# DigiCar.net
KiCad netlist of a schematic drawn in EAGLE
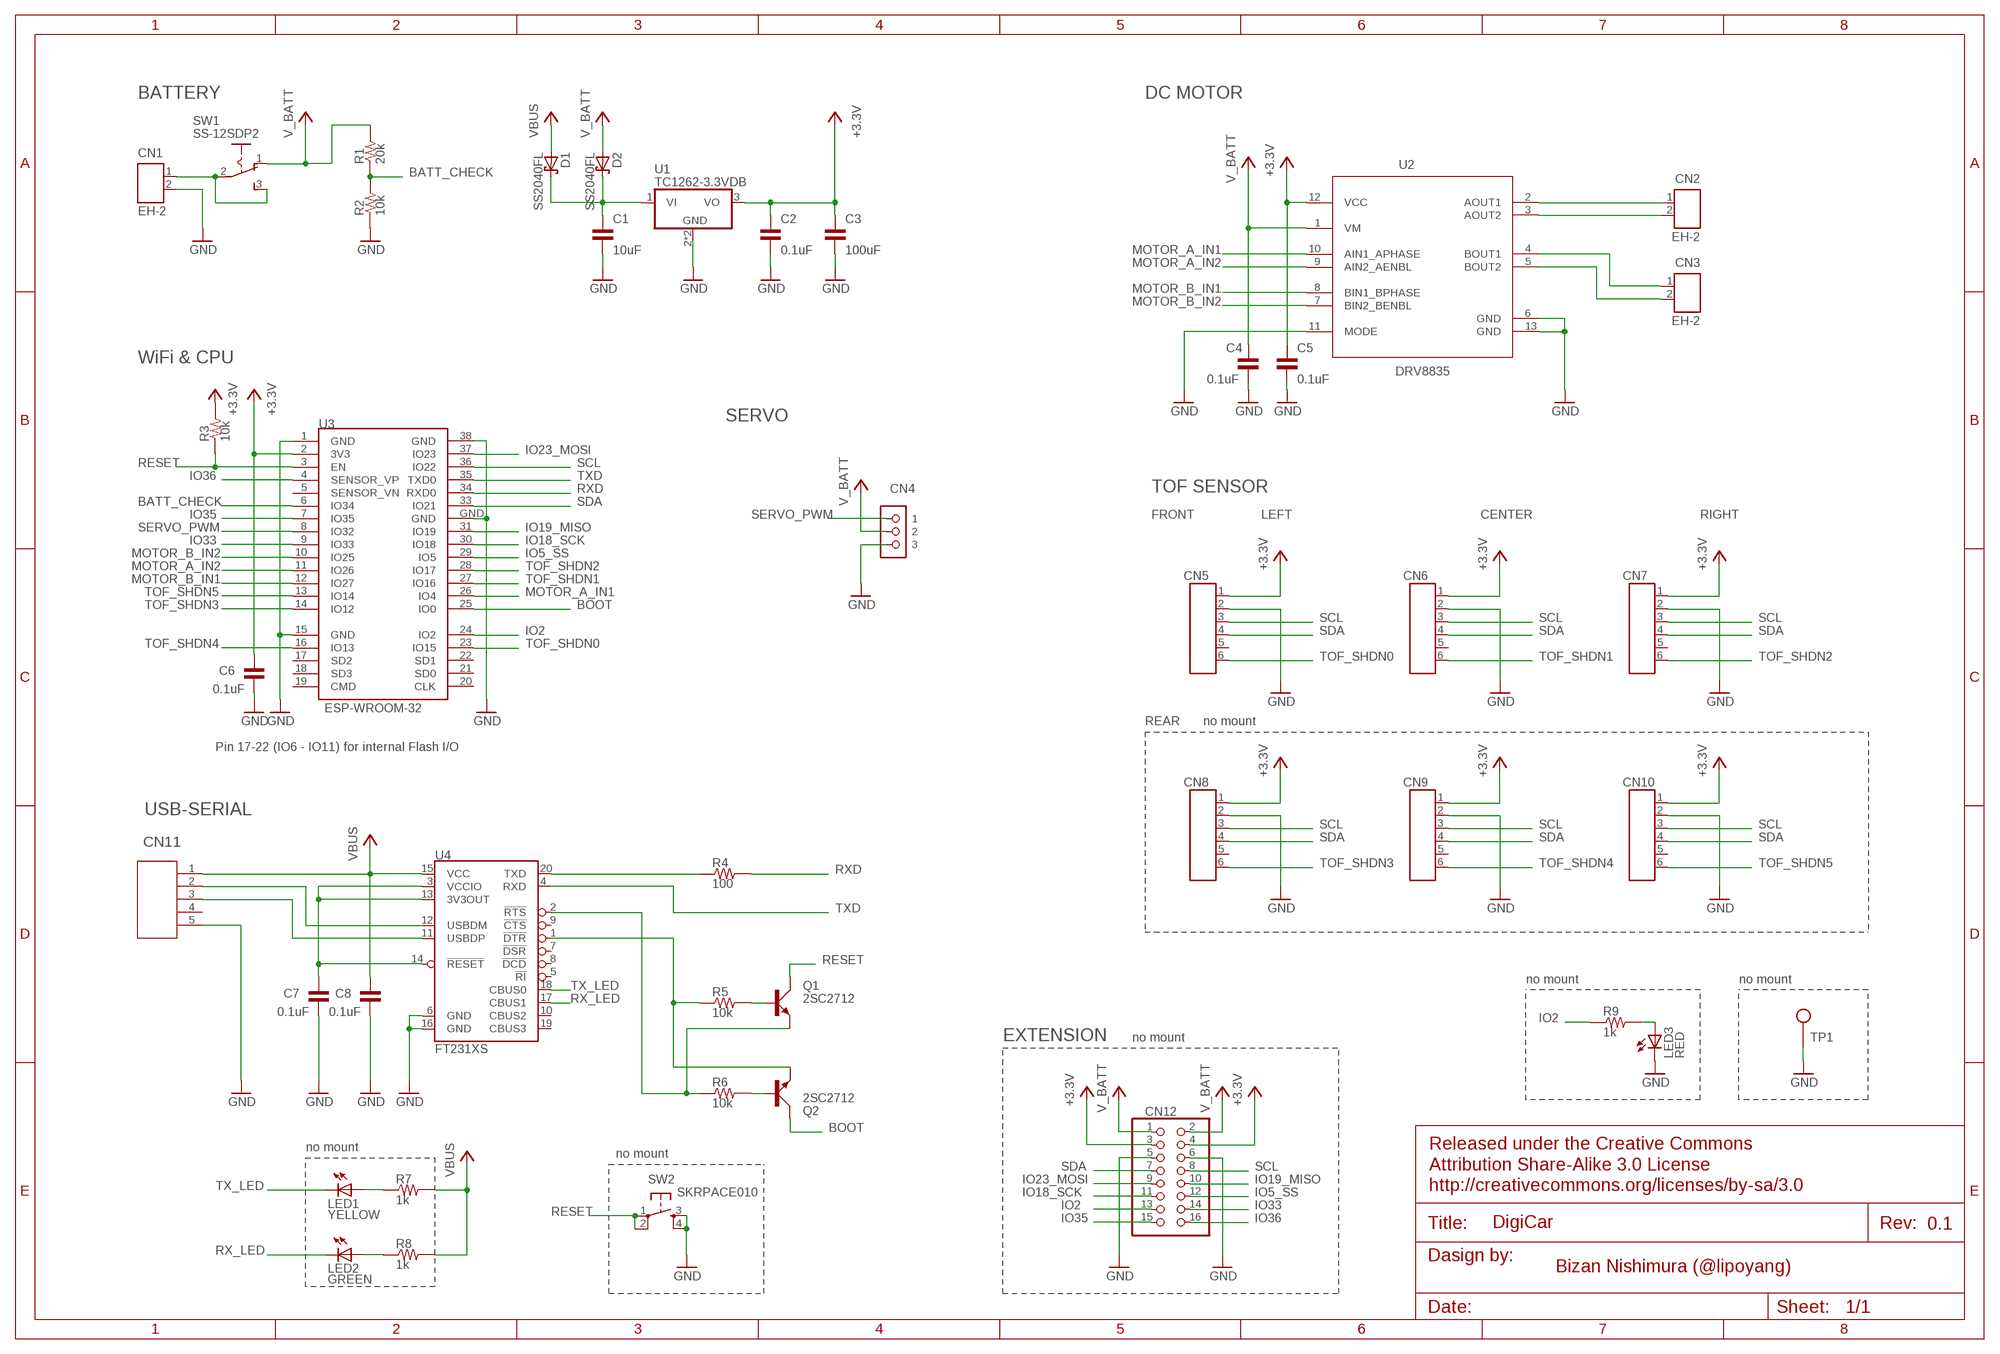
[diagram p0: schematic, sheet 1]

(export (version "E")
  (design (tool "Eeschema 10.0.6"))
  (components
    (comp (ref "C1")
      (value "10uF")
      (footprint "eagle-import:CP3216")
      (libsource (lib "eagle-import") (part "C-CP-3216"))
    )
    (comp (ref "C2")
      (value "0.1uF")
      (footprint "eagle-import:CP1608")
      (libsource (lib "eagle-import") (part "C-CP-1608"))
    )
    (comp (ref "C3")
      (value "100uF")
      (footprint "eagle-import:CP3216")
      (libsource (lib "eagle-import") (part "C-CP-3216"))
    )
    (comp (ref "C4")
      (value "0.1uF")
      (footprint "eagle-import:CP1608")
      (libsource (lib "eagle-import") (part "C-CP-1608"))
    )
    (comp (ref "C5")
      (value "0.1uF")
      (footprint "eagle-import:CP1608")
      (libsource (lib "eagle-import") (part "C-CP-1608"))
    )
    (comp (ref "C6")
      (value "0.1uF")
      (footprint "eagle-import:CP1608")
      (libsource (lib "eagle-import") (part "C-CP-1608"))
    )
    (comp (ref "C7")
      (value "0.1uF")
      (footprint "eagle-import:CP1608")
      (libsource (lib "eagle-import") (part "C-CP-1608"))
    )
    (comp (ref "C8")
      (value "0.1uF")
      (footprint "eagle-import:CP1608")
      (libsource (lib "eagle-import") (part "C-CP-1608"))
    )
    (comp (ref "CN1")
      (value "EH-2")
      (footprint "eagle-import:EH-2")
      (libsource (lib "eagle-import") (part "EH-2"))
    )
    (comp (ref "CN2")
      (value "EH-2")
      (footprint "eagle-import:EH-2")
      (libsource (lib "eagle-import") (part "EH-2"))
    )
    (comp (ref "CN3")
      (value "EH-2")
      (footprint "eagle-import:EH-2")
      (libsource (lib "eagle-import") (part "EH-2"))
    )
    (comp (ref "CN4")
      (value "PINHD-1X3")
      (footprint "eagle-import:CON_RC_SERVO")
      (libsource (lib "eagle-import") (part "PINHD-1X3"))
    )
    (comp (ref "CN5")
      (value "PINHD-1X6")
      (footprint "eagle-import:1X06")
      (libsource (lib "eagle-import") (part "PINHD-1X6"))
    )
    (comp (ref "CN6")
      (value "PINHD-1X6")
      (footprint "eagle-import:1X06")
      (libsource (lib "eagle-import") (part "PINHD-1X6"))
    )
    (comp (ref "CN7")
      (value "PINHD-1X6")
      (footprint "eagle-import:1X06")
      (libsource (lib "eagle-import") (part "PINHD-1X6"))
    )
    (comp (ref "CN8")
      (value "PINHD-1X6")
      (footprint "eagle-import:1X06")
      (libsource (lib "eagle-import") (part "PINHD-1X6"))
    )
    (comp (ref "CN9")
      (value "PINHD-1X6")
      (footprint "eagle-import:1X06")
      (libsource (lib "eagle-import") (part "PINHD-1X6"))
    )
    (comp (ref "CN10")
      (value "PINHD-1X6")
      (footprint "eagle-import:1X06")
      (libsource (lib "eagle-import") (part "PINHD-1X6"))
    )
    (comp (ref "CN11")
      (value "ZX62-B-5PA(11)")
      (footprint "eagle-import:CONN_ZX62-B-5PA(11)_HIR")
      (fields (field (name "COPYRIGHT") "Copyright (C) 2018 Accelerated Designs. All rights reserved"))
      (libsource (lib "eagle-import") (part "ZX62-B-5PA(11)"))
    )
    (comp (ref "CN12")
      (value "PINHD-2X8")
      (footprint "eagle-import:2X08")
      (libsource (lib "eagle-import") (part "PINHD-2X8"))
    )
    (comp (ref "D1")
      (value "SS2040FL")
      (footprint "eagle-import:SOD123")
      (libsource (lib "eagle-import") (part "SCHOTTKY-DIODE-SOD123"))
    )
    (comp (ref "D2")
      (value "SS2040FL")
      (footprint "eagle-import:SOD123")
      (libsource (lib "eagle-import") (part "SCHOTTKY-DIODE-SOD123"))
    )
    (comp (ref "LED1")
      (value "YELLOW")
      (footprint "eagle-import:LED1608")
      (libsource (lib "eagle-import") (part "LED1608"))
    )
    (comp (ref "LED2")
      (value "GREEN")
      (footprint "eagle-import:LED1608")
      (libsource (lib "eagle-import") (part "LED1608"))
    )
    (comp (ref "LED3")
      (value "RED")
      (footprint "eagle-import:LED1608")
      (libsource (lib "eagle-import") (part "LED1608"))
    )
    (comp (ref "Q1")
      (value "2SC2712")
      (footprint "eagle-import:SC59")
      (libsource (lib "eagle-import") (part "2SC2712"))
    )
    (comp (ref "Q2")
      (value "2SC2712")
      (footprint "eagle-import:SC59")
      (libsource (lib "eagle-import") (part "2SC2712"))
    )
    (comp (ref "R1")
      (value "20k")
      (footprint "eagle-import:CP1608")
      (libsource (lib "eagle-import") (part "R-CP-1608"))
    )
    (comp (ref "R2")
      (value "10k")
      (footprint "eagle-import:CP1608")
      (libsource (lib "eagle-import") (part "R-CP-1608"))
    )
    (comp (ref "R3")
      (value "10k")
      (footprint "eagle-import:CP1608")
      (libsource (lib "eagle-import") (part "R-CP-1608"))
    )
    (comp (ref "R4")
      (value "100")
      (footprint "eagle-import:CP1608")
      (libsource (lib "eagle-import") (part "R-CP-1608"))
    )
    (comp (ref "R5")
      (value "10k")
      (footprint "eagle-import:CP1608")
      (libsource (lib "eagle-import") (part "R-CP-1608"))
    )
    (comp (ref "R6")
      (value "10k")
      (footprint "eagle-import:CP1608")
      (libsource (lib "eagle-import") (part "R-CP-1608"))
    )
    (comp (ref "R7")
      (value "1k")
      (footprint "eagle-import:CP1608")
      (libsource (lib "eagle-import") (part "R-CP-1608"))
    )
    (comp (ref "R8")
      (value "1k")
      (footprint "eagle-import:CP1608")
      (libsource (lib "eagle-import") (part "R-CP-1608"))
    )
    (comp (ref "R9")
      (value "1k")
      (footprint "eagle-import:CP1608")
      (libsource (lib "eagle-import") (part "R-CP-1608"))
    )
    (comp (ref "SW1")
      (value "SS-12SDP2")
      (footprint "eagle-import:SLIDE-SW")
      (libsource (lib "eagle-import") (part "M251"))
    )
    (comp (ref "SW2")
      (value "SKRPACE010")
      (footprint "eagle-import:SKRPACE010")
      (libsource (lib "eagle-import") (part "SKRPACE010"))
    )
    (comp (ref "TP1")
      (value "TEST_PIN")
      (footprint "eagle-import:TEST_PIN")
      (libsource (lib "eagle-import") (part "TEST_PIN"))
    )
    (comp (ref "U1")
      (value "TC1262-3.3VDB")
      (footprint "eagle-import:SOT223")
      (libsource (lib "eagle-import") (part "TC1262-3.3VDB"))
    )
    (comp (ref "U2")
      (value "DRV8835")
      (footprint "eagle-import:DRV8835")
      (fields (field (name "MANUFACTURER") "Texas Instruments") (field (name "PARTNUMBER") "DRV8835DSSR"))
      (libsource (lib "eagle-import") (part "DRV8835"))
    )
    (comp (ref "U3")
      (value "ESP-WROOM-32")
      (footprint "eagle-import:ESP-WROOM-32")
      (libsource (lib "eagle-import") (part "ESP-WROOM-32"))
    )
    (comp (ref "U4")
      (value "FT231XS")
      (footprint "eagle-import:SSOP20")
      (libsource (lib "eagle-import") (part "FT231XS"))
    )
  )
  (nets
    (net (code "1") (name "+3.3V") (class "Default")
      (node (ref "C2") (pin "SMD1") (pinfunction "PIN1_SMD1") (pintype "passive"))
      (node (ref "C3") (pin "SMD1") (pinfunction "PIN1_SMD1") (pintype "passive"))
      (node (ref "C5") (pin "SMD1") (pinfunction "PIN1_SMD1") (pintype "passive"))
      (node (ref "C6") (pin "SMD1") (pinfunction "PIN1_SMD1") (pintype "passive"))
      (node (ref "CN10") (pin "1") (pinfunction "1_1") (pintype "bidirectional"))
      (node (ref "CN12") (pin "3") (pinfunction "3_3") (pintype "passive"))
      (node (ref "CN12") (pin "4") (pinfunction "4_4") (pintype "passive"))
      (node (ref "CN5") (pin "1") (pinfunction "1_1") (pintype "bidirectional"))
      (node (ref "CN6") (pin "1") (pinfunction "1_1") (pintype "bidirectional"))
      (node (ref "CN7") (pin "1") (pinfunction "1_1") (pintype "bidirectional"))
      (node (ref "CN8") (pin "1") (pinfunction "1_1") (pintype "bidirectional"))
      (node (ref "CN9") (pin "1") (pinfunction "1_1") (pintype "bidirectional"))
      (node (ref "R3") (pin "SMD2") (pinfunction "PIN2_SMD2") (pintype "passive"))
      (node (ref "U1") (pin "3") (pinfunction "VO_3") (pintype "passive"))
      (node (ref "U2") (pin "12") (pinfunction "VCC_12") (pintype "power_in"))
      (node (ref "U3") (pin "2") (pinfunction "3V3_2") (pintype "power_in"))
    )
    (net (code "2") (name "/BATT_CHECK") (class "Default")
      (node (ref "R1") (pin "SMD1") (pinfunction "PIN1_SMD1") (pintype "passive"))
      (node (ref "R2") (pin "SMD2") (pinfunction "PIN2_SMD2") (pintype "passive"))
      (node (ref "U3") (pin "6") (pinfunction "IO34_6") (pintype "bidirectional"))
    )
    (net (code "3") (name "/BOOT") (class "Default")
      (node (ref "Q2") (pin "C") (pinfunction "C_C") (pintype "passive"))
      (node (ref "U3") (pin "25") (pinfunction "IO0_25") (pintype "bidirectional"))
    )
    (net (code "4") (name "/IO2") (class "Default")
      (node (ref "CN12") (pin "13") (pinfunction "13_13") (pintype "passive"))
      (node (ref "R9") (pin "SMD1") (pinfunction "PIN1_SMD1") (pintype "passive"))
      (node (ref "U3") (pin "24") (pinfunction "IO2_24") (pintype "bidirectional"))
    )
    (net (code "5") (name "/IO5_SS") (class "Default")
      (node (ref "CN12") (pin "12") (pinfunction "12_12") (pintype "passive"))
      (node (ref "U3") (pin "29") (pinfunction "IO5_29") (pintype "bidirectional"))
    )
    (net (code "6") (name "/IO18_SCK") (class "Default")
      (node (ref "CN12") (pin "11") (pinfunction "11_11") (pintype "passive"))
      (node (ref "U3") (pin "30") (pinfunction "IO18_30") (pintype "bidirectional"))
    )
    (net (code "7") (name "/IO19_MISO") (class "Default")
      (node (ref "CN12") (pin "10") (pinfunction "10_10") (pintype "passive"))
      (node (ref "U3") (pin "31") (pinfunction "IO19_31") (pintype "bidirectional"))
    )
    (net (code "8") (name "/IO23_MOSI") (class "Default")
      (node (ref "CN12") (pin "9") (pinfunction "9_9") (pintype "passive"))
      (node (ref "U3") (pin "37") (pinfunction "IO23_37") (pintype "bidirectional"))
    )
    (net (code "9") (name "/IO33") (class "Default")
      (node (ref "CN12") (pin "14") (pinfunction "14_14") (pintype "passive"))
      (node (ref "U3") (pin "9") (pinfunction "IO33_9") (pintype "bidirectional"))
    )
    (net (code "10") (name "/IO35") (class "Default")
      (node (ref "CN12") (pin "15") (pinfunction "15_15") (pintype "passive"))
      (node (ref "U3") (pin "7") (pinfunction "IO35_7") (pintype "bidirectional"))
    )
    (net (code "11") (name "/IO36") (class "Default")
      (node (ref "CN12") (pin "16") (pinfunction "16_16") (pintype "passive"))
      (node (ref "U3") (pin "4") (pinfunction "SENSOR_VP_4") (pintype "bidirectional"))
    )
    (net (code "12") (name "/MOTOR_A_IN1") (class "Default")
      (node (ref "U2") (pin "10") (pinfunction "AIN1_APHASE_10") (pintype "input"))
      (node (ref "U3") (pin "26") (pinfunction "IO4_26") (pintype "bidirectional"))
    )
    (net (code "13") (name "/MOTOR_A_IN2") (class "Default")
      (node (ref "U2") (pin "9") (pinfunction "AIN2_AENBL_9") (pintype "input"))
      (node (ref "U3") (pin "11") (pinfunction "IO26_11") (pintype "bidirectional"))
    )
    (net (code "14") (name "/MOTOR_B_IN1") (class "Default")
      (node (ref "U2") (pin "8") (pinfunction "BIN1_BPHASE_8") (pintype "input"))
      (node (ref "U3") (pin "12") (pinfunction "IO27_12") (pintype "bidirectional"))
    )
    (net (code "15") (name "/MOTOR_B_IN2") (class "Default")
      (node (ref "U2") (pin "7") (pinfunction "BIN2_BENBL_7") (pintype "input"))
      (node (ref "U3") (pin "10") (pinfunction "IO25_10") (pintype "bidirectional"))
    )
    (net (code "16") (name "/RESET") (class "Default")
      (node (ref "Q1") (pin "C") (pinfunction "C_C") (pintype "passive"))
      (node (ref "R3") (pin "SMD1") (pinfunction "PIN1_SMD1") (pintype "passive"))
      (node (ref "SW2") (pin "1") (pinfunction "1_1") (pintype "passive"))
      (node (ref "SW2") (pin "2") (pinfunction "2_2") (pintype "passive"))
      (node (ref "U3") (pin "3") (pinfunction "EN_3") (pintype "input"))
    )
    (net (code "17") (name "/RXD") (class "Default")
      (node (ref "R4") (pin "SMD2") (pinfunction "PIN2_SMD2") (pintype "passive"))
      (node (ref "U3") (pin "34") (pinfunction "RXD0_34") (pintype "bidirectional"))
    )
    (net (code "18") (name "/RX_LED") (class "Default")
      (node (ref "LED2") (pin "C") (pinfunction "C_C") (pintype "passive"))
      (node (ref "U4") (pin "17") (pinfunction "CBUS1_17") (pintype "bidirectional"))
    )
    (net (code "19") (name "/SCL") (class "Default")
      (node (ref "CN10") (pin "3") (pinfunction "3_3") (pintype "bidirectional"))
      (node (ref "CN12") (pin "8") (pinfunction "8_8") (pintype "passive"))
      (node (ref "CN5") (pin "3") (pinfunction "3_3") (pintype "bidirectional"))
      (node (ref "CN6") (pin "3") (pinfunction "3_3") (pintype "bidirectional"))
      (node (ref "CN7") (pin "3") (pinfunction "3_3") (pintype "bidirectional"))
      (node (ref "CN8") (pin "3") (pinfunction "3_3") (pintype "bidirectional"))
      (node (ref "CN9") (pin "3") (pinfunction "3_3") (pintype "bidirectional"))
      (node (ref "U3") (pin "36") (pinfunction "IO22_36") (pintype "bidirectional"))
    )
    (net (code "20") (name "/SDA") (class "Default")
      (node (ref "CN10") (pin "4") (pinfunction "4_4") (pintype "bidirectional"))
      (node (ref "CN12") (pin "7") (pinfunction "7_7") (pintype "passive"))
      (node (ref "CN5") (pin "4") (pinfunction "4_4") (pintype "bidirectional"))
      (node (ref "CN6") (pin "4") (pinfunction "4_4") (pintype "bidirectional"))
      (node (ref "CN7") (pin "4") (pinfunction "4_4") (pintype "bidirectional"))
      (node (ref "CN8") (pin "4") (pinfunction "4_4") (pintype "bidirectional"))
      (node (ref "CN9") (pin "4") (pinfunction "4_4") (pintype "bidirectional"))
      (node (ref "U3") (pin "33") (pinfunction "IO21_33") (pintype "bidirectional"))
    )
    (net (code "21") (name "/SERVO_PWM") (class "Default")
      (node (ref "CN4") (pin "1") (pinfunction "1_1") (pintype "passive"))
      (node (ref "U3") (pin "8") (pinfunction "IO32_8") (pintype "bidirectional"))
    )
    (net (code "22") (name "/TOF_SHDN0") (class "Default")
      (node (ref "CN5") (pin "6") (pinfunction "6_6") (pintype "bidirectional"))
      (node (ref "U3") (pin "23") (pinfunction "IO15_23") (pintype "bidirectional"))
    )
    (net (code "23") (name "/TOF_SHDN1") (class "Default")
      (node (ref "CN6") (pin "6") (pinfunction "6_6") (pintype "bidirectional"))
      (node (ref "U3") (pin "27") (pinfunction "IO16_27") (pintype "bidirectional"))
    )
    (net (code "24") (name "/TOF_SHDN2") (class "Default")
      (node (ref "CN7") (pin "6") (pinfunction "6_6") (pintype "bidirectional"))
      (node (ref "U3") (pin "28") (pinfunction "IO17_28") (pintype "bidirectional"))
    )
    (net (code "25") (name "/TOF_SHDN3") (class "Default")
      (node (ref "CN8") (pin "6") (pinfunction "6_6") (pintype "bidirectional"))
      (node (ref "U3") (pin "14") (pinfunction "IO12_14") (pintype "bidirectional"))
    )
    (net (code "26") (name "/TOF_SHDN4") (class "Default")
      (node (ref "CN9") (pin "6") (pinfunction "6_6") (pintype "bidirectional"))
      (node (ref "U3") (pin "16") (pinfunction "IO13_16") (pintype "bidirectional"))
    )
    (net (code "27") (name "/TOF_SHDN5") (class "Default")
      (node (ref "CN10") (pin "6") (pinfunction "6_6") (pintype "bidirectional"))
      (node (ref "U3") (pin "13") (pinfunction "IO14_13") (pintype "bidirectional"))
    )
    (net (code "28") (name "/TXD") (class "Default")
      (node (ref "U3") (pin "35") (pinfunction "TXD0_35") (pintype "bidirectional"))
      (node (ref "U4") (pin "4") (pinfunction "RXD_4") (pintype "bidirectional"))
    )
    (net (code "29") (name "/TX_LED") (class "Default")
      (node (ref "LED1") (pin "C") (pinfunction "C_C") (pintype "passive"))
      (node (ref "U4") (pin "18") (pinfunction "CBUS0_18") (pintype "bidirectional"))
    )
    (net (code "30") (name "GND") (class "Default")
      (node (ref "C1") (pin "SMD2") (pinfunction "PIN2_SMD2") (pintype "passive"))
      (node (ref "C2") (pin "SMD2") (pinfunction "PIN2_SMD2") (pintype "passive"))
      (node (ref "C3") (pin "SMD2") (pinfunction "PIN2_SMD2") (pintype "passive"))
      (node (ref "C4") (pin "SMD2") (pinfunction "PIN2_SMD2") (pintype "passive"))
      (node (ref "C5") (pin "SMD2") (pinfunction "PIN2_SMD2") (pintype "passive"))
      (node (ref "C6") (pin "SMD2") (pinfunction "PIN2_SMD2") (pintype "passive"))
      (node (ref "C7") (pin "SMD2") (pinfunction "PIN2_SMD2") (pintype "passive"))
      (node (ref "C8") (pin "SMD2") (pinfunction "PIN2_SMD2") (pintype "passive"))
      (node (ref "CN1") (pin "2") (pinfunction "2_2") (pintype "bidirectional"))
      (node (ref "CN10") (pin "2") (pinfunction "2_2") (pintype "bidirectional"))
      (node (ref "CN11") (pin "5") (pinfunction "5_5") (pintype "passive"))
      (node (ref "CN12") (pin "5") (pinfunction "5_5") (pintype "passive"))
      (node (ref "CN12") (pin "6") (pinfunction "6_6") (pintype "passive"))
      (node (ref "CN4") (pin "3") (pinfunction "3_3") (pintype "passive"))
      (node (ref "CN5") (pin "2") (pinfunction "2_2") (pintype "bidirectional"))
      (node (ref "CN6") (pin "2") (pinfunction "2_2") (pintype "bidirectional"))
      (node (ref "CN7") (pin "2") (pinfunction "2_2") (pintype "bidirectional"))
      (node (ref "CN8") (pin "2") (pinfunction "2_2") (pintype "bidirectional"))
      (node (ref "CN9") (pin "2") (pinfunction "2_2") (pintype "bidirectional"))
      (node (ref "LED3") (pin "C") (pinfunction "C_C") (pintype "passive"))
      (node (ref "R2") (pin "SMD1") (pinfunction "PIN1_SMD1") (pintype "passive"))
      (node (ref "SW2") (pin "3") (pinfunction "3_3") (pintype "passive"))
      (node (ref "SW2") (pin "4") (pinfunction "4_4") (pintype "passive"))
      (node (ref "TP1") (pin "1") (pinfunction "P$1_1") (pintype "bidirectional"))
      (node (ref "U1") (pin "2") (pinfunction "GND_2") (pintype "passive"))
      (node (ref "U1") (pin "4") (pinfunction "GND_4") (pintype "passive"))
      (node (ref "U2") (pin "11") (pinfunction "MODE_11") (pintype "input"))
      (node (ref "U2") (pin "13") (pinfunction "GND_13") (pintype "power_in"))
      (node (ref "U2") (pin "6") (pinfunction "GND_6") (pintype "power_in"))
      (node (ref "U3") (pin "1") (pinfunction "GND_1") (pintype "power_in"))
      (node (ref "U3") (pin "15") (pinfunction "GND_15") (pintype "power_in"))
      (node (ref "U3") (pin "38") (pinfunction "GND_38") (pintype "power_in"))
      (node (ref "U3") (pin "GND") (pinfunction "GND_GND") (pintype "power_in"))
      (node (ref "U4") (pin "16") (pinfunction "GND_16") (pintype "bidirectional"))
      (node (ref "U4") (pin "6") (pinfunction "GND_6") (pintype "bidirectional"))
    )
    (net (code "31") (name "Net-(C1-PIN1)") (class "Default")
      (node (ref "C1") (pin "SMD1") (pinfunction "PIN1_SMD1") (pintype "passive"))
      (node (ref "D1") (pin "C") (pinfunction "C_C") (pintype "passive"))
      (node (ref "D2") (pin "C") (pinfunction "C_C") (pintype "passive"))
      (node (ref "U1") (pin "1") (pinfunction "VI_1") (pintype "input"))
    )
    (net (code "32") (name "Net-(C7-PIN1)") (class "Default")
      (node (ref "C7") (pin "SMD1") (pinfunction "PIN1_SMD1") (pintype "passive"))
      (node (ref "U4") (pin "13") (pinfunction "3V3OUT_13") (pintype "bidirectional"))
      (node (ref "U4") (pin "14") (pinfunction "~{RESET}_14") (pintype "bidirectional"))
      (node (ref "U4") (pin "3") (pinfunction "VCCIO_3") (pintype "bidirectional"))
    )
    (net (code "33") (name "Net-(R4-PIN1)") (class "Default")
      (node (ref "R4") (pin "SMD1") (pinfunction "PIN1_SMD1") (pintype "passive"))
      (node (ref "U4") (pin "20") (pinfunction "TXD_20") (pintype "bidirectional"))
    )
    (net (code "34") (name "Net-(R5-PIN1)") (class "Default")
      (node (ref "Q2") (pin "E") (pinfunction "E_E") (pintype "passive"))
      (node (ref "R5") (pin "SMD1") (pinfunction "PIN1_SMD1") (pintype "passive"))
      (node (ref "U4") (pin "1") (pinfunction "~{DTR}_1") (pintype "bidirectional"))
    )
    (net (code "35") (name "Net-(R5-PIN2)") (class "Default")
      (node (ref "Q1") (pin "B") (pinfunction "B_B") (pintype "passive"))
      (node (ref "R5") (pin "SMD2") (pinfunction "PIN2_SMD2") (pintype "passive"))
    )
    (net (code "36") (name "Net-(R6-PIN1)") (class "Default")
      (node (ref "Q1") (pin "E") (pinfunction "E_E") (pintype "passive"))
      (node (ref "R6") (pin "SMD1") (pinfunction "PIN1_SMD1") (pintype "passive"))
      (node (ref "U4") (pin "2") (pinfunction "~{RTS}_2") (pintype "bidirectional"))
    )
    (net (code "37") (name "Net-(R6-PIN2)") (class "Default")
      (node (ref "Q2") (pin "B") (pinfunction "B_B") (pintype "passive"))
      (node (ref "R6") (pin "SMD2") (pinfunction "PIN2_SMD2") (pintype "passive"))
    )
    (net (code "38") (name "Net-(R7-PIN1)") (class "Default")
      (node (ref "LED1") (pin "A") (pinfunction "A_A") (pintype "passive"))
      (node (ref "R7") (pin "SMD1") (pinfunction "PIN1_SMD1") (pintype "passive"))
    )
    (net (code "39") (name "Net-(R8-PIN1)") (class "Default")
      (node (ref "LED2") (pin "A") (pinfunction "A_A") (pintype "passive"))
      (node (ref "R8") (pin "SMD1") (pinfunction "PIN1_SMD1") (pintype "passive"))
    )
    (net (code "40") (name "Net-(R9-PIN2)") (class "Default")
      (node (ref "LED3") (pin "A") (pinfunction "A_A") (pintype "passive"))
      (node (ref "R9") (pin "SMD2") (pinfunction "PIN2_SMD2") (pintype "passive"))
    )
    (net (code "41") (name "Net-(SW1-P)") (class "Default")
      (node (ref "CN1") (pin "1") (pinfunction "1_1") (pintype "bidirectional"))
      (node (ref "SW1") (pin "2") (pinfunction "P_2") (pintype "passive"))
      (node (ref "SW1") (pin "3") (pinfunction "S_3") (pintype "passive"))
    )
    (net (code "42") (name "Net-(U2-AOUT1)") (class "Default")
      (node (ref "CN2") (pin "1") (pinfunction "1_1") (pintype "bidirectional"))
      (node (ref "U2") (pin "2") (pinfunction "AOUT1_2") (pintype "output"))
    )
    (net (code "43") (name "Net-(U2-AOUT2)") (class "Default")
      (node (ref "CN2") (pin "2") (pinfunction "2_2") (pintype "bidirectional"))
      (node (ref "U2") (pin "3") (pinfunction "AOUT2_3") (pintype "output"))
    )
    (net (code "44") (name "Net-(U2-BOUT1)") (class "Default")
      (node (ref "CN3") (pin "1") (pinfunction "1_1") (pintype "bidirectional"))
      (node (ref "U2") (pin "4") (pinfunction "BOUT1_4") (pintype "output"))
    )
    (net (code "45") (name "Net-(U2-BOUT2)") (class "Default")
      (node (ref "CN3") (pin "2") (pinfunction "2_2") (pintype "bidirectional"))
      (node (ref "U2") (pin "5") (pinfunction "BOUT2_5") (pintype "output"))
    )
    (net (code "46") (name "Net-(U4-USBDM)") (class "Default")
      (node (ref "CN11") (pin "2") (pinfunction "2_2") (pintype "passive"))
      (node (ref "U4") (pin "12") (pinfunction "USBDM_12") (pintype "bidirectional"))
    )
    (net (code "47") (name "Net-(U4-USBDP)") (class "Default")
      (node (ref "CN11") (pin "3") (pinfunction "3_3") (pintype "passive"))
      (node (ref "U4") (pin "11") (pinfunction "USBDP_11") (pintype "bidirectional"))
    )
    (net (code "48") (name "VBUS") (class "Default")
      (node (ref "C8") (pin "SMD1") (pinfunction "PIN1_SMD1") (pintype "passive"))
      (node (ref "CN11") (pin "1") (pinfunction "1_1") (pintype "passive"))
      (node (ref "D1") (pin "A") (pinfunction "A_A") (pintype "passive"))
      (node (ref "R7") (pin "SMD2") (pinfunction "PIN2_SMD2") (pintype "passive"))
      (node (ref "R8") (pin "SMD2") (pinfunction "PIN2_SMD2") (pintype "passive"))
      (node (ref "U4") (pin "15") (pinfunction "VCC_15") (pintype "bidirectional"))
    )
    (net (code "49") (name "V_BATT") (class "Default")
      (node (ref "C4") (pin "SMD1") (pinfunction "PIN1_SMD1") (pintype "passive"))
      (node (ref "CN12") (pin "1") (pinfunction "1_1") (pintype "passive"))
      (node (ref "CN12") (pin "2") (pinfunction "2_2") (pintype "passive"))
      (node (ref "CN4") (pin "2") (pinfunction "2_2") (pintype "passive"))
      (node (ref "D2") (pin "A") (pinfunction "A_A") (pintype "passive"))
      (node (ref "R1") (pin "SMD2") (pinfunction "PIN2_SMD2") (pintype "passive"))
      (node (ref "SW1") (pin "1") (pinfunction "O_1") (pintype "passive"))
      (node (ref "U2") (pin "1") (pinfunction "VM_1") (pintype "power_in"))
    )
    (net (code "50") (name "unconnected-(CN5-Pad5)") (class "Default")
      (node (ref "CN5") (pin "5") (pinfunction "5_5") (pintype "bidirectional"))
    )
    (net (code "51") (name "unconnected-(CN6-Pad5)") (class "Default")
      (node (ref "CN6") (pin "5") (pinfunction "5_5") (pintype "bidirectional"))
    )
    (net (code "52") (name "unconnected-(CN7-Pad5)") (class "Default")
      (node (ref "CN7") (pin "5") (pinfunction "5_5") (pintype "bidirectional"))
    )
    (net (code "53") (name "unconnected-(CN8-Pad5)") (class "Default")
      (node (ref "CN8") (pin "5") (pinfunction "5_5") (pintype "bidirectional"))
    )
    (net (code "54") (name "unconnected-(CN9-Pad5)") (class "Default")
      (node (ref "CN9") (pin "5") (pinfunction "5_5") (pintype "bidirectional"))
    )
    (net (code "55") (name "unconnected-(CN10-Pad5)") (class "Default")
      (node (ref "CN10") (pin "5") (pinfunction "5_5") (pintype "bidirectional"))
    )
    (net (code "56") (name "unconnected-(CN11-Pad4)") (class "Default")
      (node (ref "CN11") (pin "4") (pinfunction "4_4") (pintype "passive"))
    )
    (net (code "57") (name "unconnected-(U3-CLK-Pad20)") (class "Default")
      (node (ref "U3") (pin "20") (pinfunction "CLK_20") (pintype "bidirectional"))
    )
    (net (code "58") (name "unconnected-(U3-CMD-Pad19)") (class "Default")
      (node (ref "U3") (pin "19") (pinfunction "CMD_19") (pintype "bidirectional"))
    )
    (net (code "59") (name "unconnected-(U3-SD0-Pad21)") (class "Default")
      (node (ref "U3") (pin "21") (pinfunction "SD0_21") (pintype "bidirectional"))
    )
    (net (code "60") (name "unconnected-(U3-SD1-Pad22)") (class "Default")
      (node (ref "U3") (pin "22") (pinfunction "SD1_22") (pintype "bidirectional"))
    )
    (net (code "61") (name "unconnected-(U3-SD2-Pad17)") (class "Default")
      (node (ref "U3") (pin "17") (pinfunction "SD2_17") (pintype "bidirectional"))
    )
    (net (code "62") (name "unconnected-(U3-SD3-Pad18)") (class "Default")
      (node (ref "U3") (pin "18") (pinfunction "SD3_18") (pintype "bidirectional"))
    )
    (net (code "63") (name "unconnected-(U3-SENSOR_VN-Pad5)") (class "Default")
      (node (ref "U3") (pin "5") (pinfunction "SENSOR_VN_5") (pintype "bidirectional"))
    )
    (net (code "64") (name "unconnected-(U4-CBUS2-Pad10)") (class "Default")
      (node (ref "U4") (pin "10") (pinfunction "CBUS2_10") (pintype "bidirectional"))
    )
    (net (code "65") (name "unconnected-(U4-CBUS3-Pad19)") (class "Default")
      (node (ref "U4") (pin "19") (pinfunction "CBUS3_19") (pintype "bidirectional"))
    )
    (net (code "66") (name "unconnected-(U4-~{CTS}-Pad9)") (class "Default")
      (node (ref "U4") (pin "9") (pinfunction "~{CTS}_9") (pintype "bidirectional"))
    )
    (net (code "67") (name "unconnected-(U4-~{DCD}-Pad8)") (class "Default")
      (node (ref "U4") (pin "8") (pinfunction "~{DCD}_8") (pintype "bidirectional"))
    )
    (net (code "68") (name "unconnected-(U4-~{DSR}-Pad7)") (class "Default")
      (node (ref "U4") (pin "7") (pinfunction "~{DSR}_7") (pintype "bidirectional"))
    )
    (net (code "69") (name "unconnected-(U4-~{RI}-Pad5)") (class "Default")
      (node (ref "U4") (pin "5") (pinfunction "~{RI}_5") (pintype "bidirectional"))
    )
  )
)
